# DDS_DAC.net
KiCad netlist of a schematic drawn in Altium Designer
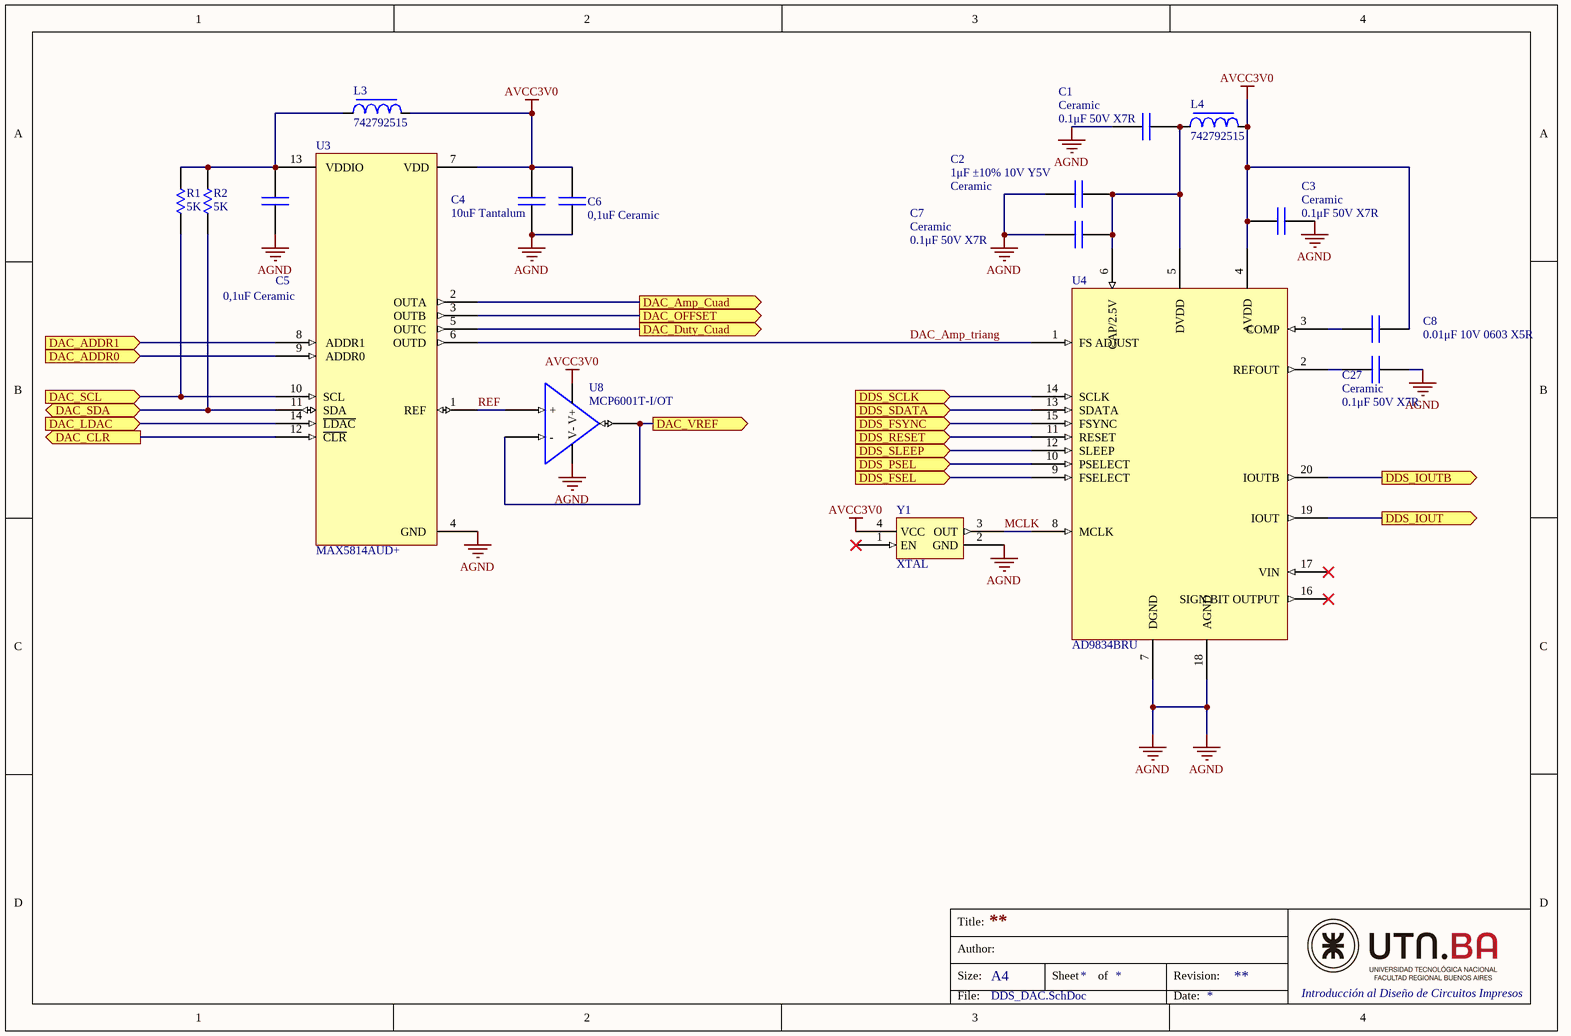
[diagram p0: DDS_DAC.SchDoc]

(export (version "E")
  (design (tool "Eeschema 10.0.6"))
  (components
    (comp (ref "C1")
      (value "0.1μF 50V X7R")
      (footprint "C_0805")
      (description "Capacitor")
      (fields (field (name "TYPE") "Ceramic"))
      (libsource (lib "Gen_func") (part "Cap"))
    )
    (comp (ref "C2")
      (value "1μF ±10% 10V Y5V")
      (footprint "C_0805")
      (description "Capacitor")
      (fields (field (name "TYPE") "Ceramic"))
      (libsource (lib "Gen_func") (part "Cap"))
    )
    (comp (ref "C3")
      (value "0.1μF 50V X7R")
      (footprint "C_0805")
      (description "Capacitor")
      (fields (field (name "TYPE") "Ceramic"))
      (libsource (lib "Gen_func") (part "Cap"))
    )
    (comp (ref "C4")
      (value "10uF Tantalum")
      (footprint "C_0805")
      (description "Capacitor")
      (libsource (lib "Gen_func") (part "Cap"))
    )
    (comp (ref "C5")
      (value "0,1uF Ceramic")
      (footprint "C_0805")
      (description "Capacitor")
      (libsource (lib "Gen_func") (part "Cap"))
    )
    (comp (ref "C6")
      (value "0,1uF Ceramic")
      (footprint "C_0805")
      (description "Capacitor")
      (libsource (lib "Gen_func") (part "Cap"))
    )
    (comp (ref "C7")
      (value "0.1μF 50V X7R")
      (footprint "C_0805")
      (description "Capacitor")
      (fields (field (name "TYPE") "Ceramic"))
      (libsource (lib "Gen_func") (part "Cap"))
    )
    (comp (ref "C8")
      (value "0.01μF 10V 0603 X5R")
      (footprint "C_0805")
      (description "Capacitor")
      (libsource (lib "Gen_func") (part "Cap"))
    )
    (comp (ref "C27")
      (value "0.1μF 50V X7R")
      (footprint "C_0805")
      (description "Capacitor")
      (fields (field (name "TYPE") "Ceramic"))
      (libsource (lib "Gen_func") (part "Cap"))
    )
    (comp (ref "L3")
      (value "742792515")
      (footprint "L_1812")
      (description "Ferrite Bead")
      (libsource (lib "Gen_func") (part "Ferrite"))
    )
    (comp (ref "L4")
      (value "742792515")
      (footprint "L_1812")
      (description "Ferrite Bead")
      (libsource (lib "Gen_func") (part "Ferrite"))
    )
    (comp (ref "R1")
      (value "5K")
      (footprint "R_0805")
      (description "Resistor")
      (libsource (lib "Gen_func") (part "Res"))
    )
    (comp (ref "R2")
      (value "5K")
      (footprint "R_0805")
      (description "Resistor")
      (libsource (lib "Gen_func") (part "Res"))
    )
    (comp (ref "U3")
      (value "MAX5814AUD+")
      (description "DAC x4 I2C")
      (libsource (lib "Gen_func") (part "DAC_14Leads"))
    )
    (comp (ref "U4")
      (value "AD9834BRU")
      (footprint "TSSOP_20")
      (description "DDS 50MHz")
      (libsource (lib "Gen_func") (part "DDS"))
    )
    (comp (ref "U8")
      (value "MCP6001T-I/OT")
      (footprint "SOT_23")
      (description "OpAmp")
      (libsource (lib "Gen_func") (part "OpAmp"))
    )
    (comp (ref "Y1")
      (value "XTAL")
      (footprint "XTAL_4")
      (description "Crystal oscillator")
      (libsource (lib "Gen_func") (part "XTAL"))
    )
  )
  (nets
    (net (code "1") (name "/DAC_ADDR0") (class "Default")
      (node (ref "U3") (pin "9") (pinfunction "ADDR0_9") (pintype "input"))
    )
    (net (code "2") (name "/DAC_ADDR1") (class "Default")
      (node (ref "U3") (pin "8") (pinfunction "ADDR1_8") (pintype "input"))
    )
    (net (code "3") (name "/DAC_Amp_Cuad") (class "Default")
      (node (ref "U3") (pin "2") (pinfunction "OUTA_2") (pintype "output"))
    )
    (net (code "4") (name "/DAC_Amp_triang") (class "Default")
      (node (ref "U3") (pin "6") (pinfunction "OUTD_6") (pintype "output"))
      (node (ref "U4") (pin "1") (pinfunction "FS_ADJUST_1") (pintype "input"))
    )
    (net (code "5") (name "/DAC_CLR") (class "Default")
      (node (ref "U3") (pin "12") (pinfunction "~{CLR}_12") (pintype "input"))
    )
    (net (code "6") (name "/DAC_Duty_Cuad") (class "Default")
      (node (ref "U3") (pin "5") (pinfunction "OUTC_5") (pintype "output"))
    )
    (net (code "7") (name "/DAC_LDAC") (class "Default")
      (node (ref "U3") (pin "14") (pinfunction "~{LDAC}_14") (pintype "input"))
    )
    (net (code "8") (name "/DAC_OFFSET") (class "Default")
      (node (ref "U3") (pin "3") (pinfunction "OUTB_3") (pintype "output"))
    )
    (net (code "9") (name "/DAC_SCL") (class "Default")
      (node (ref "R1") (pin "1") (pinfunction "1_1") (pintype "passive"))
      (node (ref "U3") (pin "10") (pinfunction "SCL_10") (pintype "input"))
    )
    (net (code "10") (name "/DAC_SDA") (class "Default")
      (node (ref "R2") (pin "1") (pinfunction "1_1") (pintype "passive"))
      (node (ref "U3") (pin "11") (pinfunction "SDA_11") (pintype "bidirectional"))
    )
    (net (code "11") (name "/DAC_VREF") (class "Default")
      (node (ref "U8") (pin "1") (pinfunction "Vout_1") (pintype "bidirectional"))
      (node (ref "U8") (pin "4") (pinfunction "-_4") (pintype "input"))
    )
    (net (code "12") (name "/DDS_FSEL") (class "Default")
      (node (ref "U4") (pin "9") (pinfunction "FSELECT_9") (pintype "input"))
    )
    (net (code "13") (name "/DDS_FSYNC") (class "Default")
      (node (ref "U4") (pin "15") (pinfunction "FSYNC_15") (pintype "input"))
    )
    (net (code "14") (name "/DDS_IOUT") (class "Default")
      (node (ref "U4") (pin "19") (pinfunction "IOUT_19") (pintype "output"))
    )
    (net (code "15") (name "/DDS_IOUTB") (class "Default")
      (node (ref "U4") (pin "20") (pinfunction "IOUTB_20") (pintype "output"))
    )
    (net (code "16") (name "/DDS_PSEL") (class "Default")
      (node (ref "U4") (pin "10") (pinfunction "PSELECT_10") (pintype "input"))
    )
    (net (code "17") (name "/DDS_RESET") (class "Default")
      (node (ref "U4") (pin "11") (pinfunction "RESET_11") (pintype "input"))
    )
    (net (code "18") (name "/DDS_SCLK") (class "Default")
      (node (ref "U4") (pin "14") (pinfunction "SCLK_14") (pintype "input"))
    )
    (net (code "19") (name "/DDS_SDATA") (class "Default")
      (node (ref "U4") (pin "13") (pinfunction "SDATA_13") (pintype "input"))
    )
    (net (code "20") (name "/DDS_SLEEP") (class "Default")
      (node (ref "U4") (pin "12") (pinfunction "SLEEP_12") (pintype "input"))
    )
    (net (code "21") (name "/MCLK") (class "Default")
      (node (ref "U4") (pin "8") (pinfunction "MCLK_8") (pintype "input"))
      (node (ref "Y1") (pin "3") (pinfunction "OUT_3") (pintype "output"))
    )
    (net (code "22") (name "/REF") (class "Default")
      (node (ref "U3") (pin "1") (pinfunction "REF_1") (pintype "bidirectional"))
      (node (ref "U8") (pin "3") (pinfunction "+_3") (pintype "input"))
    )
    (net (code "23") (name "AGND") (class "Default")
      (node (ref "C1") (pin "1") (pinfunction "1_1") (pintype "passive"))
      (node (ref "C2") (pin "1") (pinfunction "1_1") (pintype "passive"))
      (node (ref "C27") (pin "2") (pinfunction "2_2") (pintype "passive"))
      (node (ref "C3") (pin "2") (pinfunction "2_2") (pintype "passive"))
      (node (ref "C4") (pin "2") (pinfunction "2_2") (pintype "passive"))
      (node (ref "C5") (pin "2") (pinfunction "2_2") (pintype "passive"))
      (node (ref "C6") (pin "2") (pinfunction "2_2") (pintype "passive"))
      (node (ref "C7") (pin "1") (pinfunction "1_1") (pintype "passive"))
      (node (ref "U3") (pin "4") (pinfunction "GND_4") (pintype "power_in"))
      (node (ref "U4") (pin "18") (pinfunction "AGND_18") (pintype "power_in"))
      (node (ref "U4") (pin "7") (pinfunction "DGND_7") (pintype "power_in"))
      (node (ref "U8") (pin "2") (pinfunction "V-_2") (pintype "power_in"))
      (node (ref "Y1") (pin "2") (pinfunction "GND_2") (pintype "power_in"))
    )
    (net (code "24") (name "AVCC3V0") (class "Default")
      (node (ref "C3") (pin "1") (pinfunction "1_1") (pintype "passive"))
      (node (ref "C4") (pin "1") (pinfunction "1_1") (pintype "passive"))
      (node (ref "C6") (pin "1") (pinfunction "1_1") (pintype "passive"))
      (node (ref "C8") (pin "1") (pinfunction "1_1") (pintype "passive"))
      (node (ref "L3") (pin "2") (pinfunction "2_2") (pintype "passive"))
      (node (ref "L4") (pin "2") (pinfunction "2_2") (pintype "passive"))
      (node (ref "U3") (pin "7") (pinfunction "VDD_7") (pintype "power_in"))
      (node (ref "U4") (pin "4") (pinfunction "AVDD_4") (pintype "power_in"))
      (node (ref "U8") (pin "5") (pinfunction "V+_5") (pintype "power_in"))
      (node (ref "Y1") (pin "4") (pinfunction "VCC_4") (pintype "power_in"))
    )
    (net (code "25") (name "Net-(U3-VDDIO)") (class "Default")
      (node (ref "C5") (pin "1") (pinfunction "1_1") (pintype "passive"))
      (node (ref "L3") (pin "1") (pinfunction "1_1") (pintype "passive"))
      (node (ref "R1") (pin "2") (pinfunction "2_2") (pintype "passive"))
      (node (ref "R2") (pin "2") (pinfunction "2_2") (pintype "passive"))
      (node (ref "U3") (pin "13") (pinfunction "VDDIO_13") (pintype "power_in"))
    )
    (net (code "26") (name "Net-(U4-CAP{slash}2.5V)") (class "Default")
      (node (ref "C1") (pin "2") (pinfunction "2_2") (pintype "passive"))
      (node (ref "C2") (pin "2") (pinfunction "2_2") (pintype "passive"))
      (node (ref "C7") (pin "2") (pinfunction "2_2") (pintype "passive"))
      (node (ref "L4") (pin "1") (pinfunction "1_1") (pintype "passive"))
      (node (ref "U4") (pin "5") (pinfunction "DVDD_5") (pintype "power_in"))
      (node (ref "U4") (pin "6") (pinfunction "CAP/2.5V_6") (pintype "input"))
    )
    (net (code "27") (name "Net-(U4-COMP)") (class "Default")
      (node (ref "C8") (pin "2") (pinfunction "2_2") (pintype "passive"))
      (node (ref "U4") (pin "3") (pinfunction "COMP_3") (pintype "input"))
    )
    (net (code "28") (name "Net-(U4-REFOUT)") (class "Default")
      (node (ref "C27") (pin "1") (pinfunction "1_1") (pintype "passive"))
      (node (ref "U4") (pin "2") (pinfunction "REFOUT_2") (pintype "output"))
    )
    (net (code "29") (name "unconnected-(U4-SIGN_BIT_OUTPUT-Pad16)") (class "Default")
      (node (ref "U4") (pin "16") (pinfunction "SIGN_BIT_OUTPUT_16") (pintype "output+no_connect"))
    )
    (net (code "30") (name "unconnected-(U4-VIN-Pad17)") (class "Default")
      (node (ref "U4") (pin "17") (pinfunction "VIN_17") (pintype "input+no_connect"))
    )
    (net (code "31") (name "unconnected-(Y1-EN-Pad1)") (class "Default")
      (node (ref "Y1") (pin "1") (pinfunction "EN_1") (pintype "input+no_connect"))
    )
  )
)
